# analog_sensor_input.net
KiCad netlist of a schematic drawn in Altium Designer
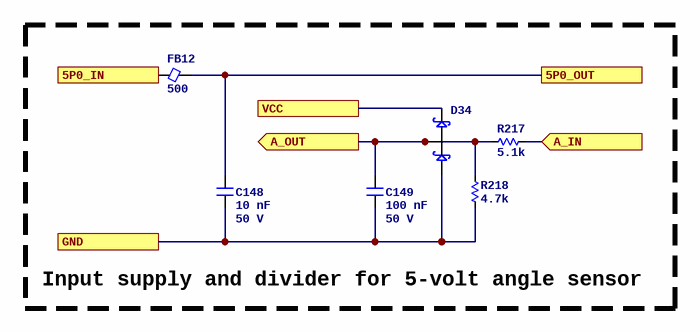
[diagram p0: analog_sensor_input.SchDoc]

(export (version "E")
  (design (tool "Eeschema 10.0.6"))
  (components
    (comp (ref "C148")
      (value "CL05B103KB5NNNC")
      (footprint "C0402")
      (fields
        (field (name "CAPACITANCE") "10 nF")
        (field (name "MANUFACTURER") "Samsung Electro-Mechanics")
        (field (name "VOLTAGE RATING") "50 V")
      )
      (libsource (lib "database") (part "__template_cap"))
    )
    (comp (ref "C149")
      (value "CL05B104KB54PNC")
      (footprint "C0402")
      (fields
        (field (name "CAPACITANCE") "100 nF")
        (field (name "MANUFACTURER") "Samsung Electro-Mechanics")
        (field (name "VOLTAGE RATING") "50 V")
      )
      (libsource (lib "database") (part "__template_cap"))
    )
    (comp (ref "D34")
      (value "BAT54SLT1G")
      (footprint "3SOT23")
      (description "DIODE SCHOTTKY DUAL 30V SOT23")
      (fields (field (name "MANUFACTURER") "ON Semiconductor"))
      (libsource (lib "database") (part "BAT54SLT1G"))
    )
    (comp (ref "FB12")
      (value "BLM15AX601SN1D")
      (footprint "FB0402")
      (fields (field (name "MANUFACTURER") "Murata Electronics") (field (name "CURRENT RATING (MA)") "500"))
      (libsource (lib "database") (part "__template_fb"))
    )
    (comp (ref "R217")
      (value "5.1k")
      (footprint "R0402")
      (fields
        (field (name "TOLERANCE") "1%")
        (field (name "MANUFACTURER PART NUMBER") "0402WGF5101TCE")
        (field (name "MANUFACTURER") "UNI-ROYAL(Uniroyal Elec)")
      )
      (libsource (lib "database") (part "__template_resistor"))
    )
    (comp (ref "R218")
      (value "4.7k")
      (footprint "R0402")
      (fields
        (field (name "TOLERANCE") "1%")
        (field (name "MANUFACTURER PART NUMBER") "0402WGF4701TCE")
        (field (name "MANUFACTURER") "UNI-ROYAL(Uniroyal Elec)")
      )
      (libsource (lib "database") (part "__template_resistor"))
    )
  )
  (nets
    (net (code "1") (name "/5P0_IN") (class "Default") (node (ref "FB12") (pin "1") (pintype "passive")))
    (net (code "2") (name "/5P0_OUT") (class "Default")
      (node (ref "C148") (pin "1") (pintype "passive"))
      (node (ref "FB12") (pin "2") (pintype "passive"))
    )
    (net (code "3") (name "/A_IN") (class "Default") (node (ref "R217") (pin "2") (pintype "passive")))
    (net (code "4") (name "/A_OUT") (class "Default")
      (node (ref "C149") (pin "1") (pintype "passive"))
      (node (ref "D34") (pin "3") (pintype "passive"))
      (node (ref "R217") (pin "1") (pintype "passive"))
      (node (ref "R218") (pin "2") (pintype "passive"))
    )
    (net (code "5") (name "/GND") (class "Default")
      (node (ref "C148") (pin "2") (pintype "passive"))
      (node (ref "C149") (pin "2") (pintype "passive"))
      (node (ref "D34") (pin "1") (pintype "passive"))
      (node (ref "R218") (pin "1") (pintype "passive"))
    )
    (net (code "6") (name "/VCC") (class "Default") (node (ref "D34") (pin "2") (pintype "passive")))
  )
)
